# KD_Board.net
KiCad netlist of a schematic drawn in EAGLE
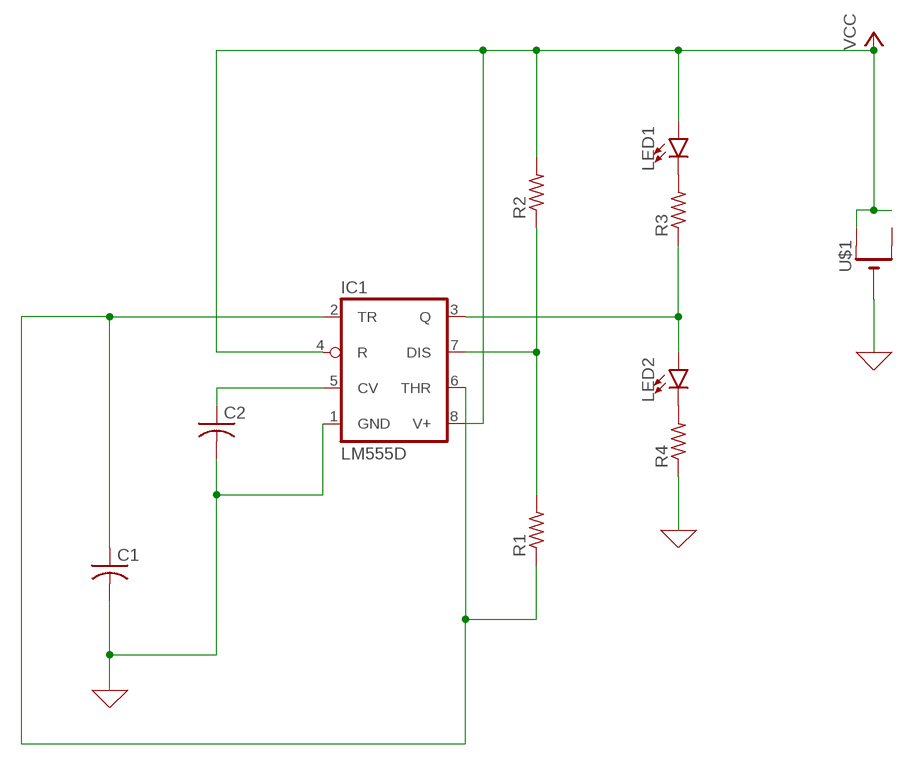
[diagram p0: schematic, sheet 1]

(export (version "E")
  (design (tool "Eeschema 10.0.6"))
  (components
    (comp (ref "C1")
      (value "C-USC0805K")
      (footprint "eagle-import:C0805K")
      (libsource (lib "eagle-import") (part "C-USC0805K"))
    )
    (comp (ref "C2")
      (value "C-USC0805K")
      (footprint "eagle-import:C0805K")
      (libsource (lib "eagle-import") (part "C-USC0805K"))
    )
    (comp (ref "IC1")
      (value "LM555D")
      (footprint "eagle-import:SO08")
      (libsource (lib "eagle-import") (part "555DLM"))
    )
    (comp (ref "LED1")
      (value "LED")
      (footprint "eagle-import:LED_5MM")
      (libsource (lib "eagle-import") (part "LED"))
    )
    (comp (ref "LED2")
      (value "LED")
      (footprint "eagle-import:LED_5MM")
      (libsource (lib "eagle-import") (part "LED"))
    )
    (comp (ref "R1")
      (value "R-US_M0805")
      (footprint "eagle-import:M0805")
      (libsource (lib "eagle-import") (part "R-US_M0805"))
    )
    (comp (ref "R2")
      (value "R-US_M0805")
      (footprint "eagle-import:M0805")
      (libsource (lib "eagle-import") (part "R-US_M0805"))
    )
    (comp (ref "R3")
      (value "R-US_M0805")
      (footprint "eagle-import:M0805")
      (libsource (lib "eagle-import") (part "R-US_M0805"))
    )
    (comp (ref "R4")
      (value "R-US_M0805")
      (footprint "eagle-import:M0805")
      (libsource (lib "eagle-import") (part "R-US_M0805"))
    )
    (comp (ref "U$1")
      (value "CR1220THM")
      (footprint "eagle-import:CR1220-THM")
      (libsource (lib "eagle-import") (part "CR1220THM"))
    )
  )
  (nets
    (net (code "1") (name "GND") (class "Default")
      (node (ref "C1") (pin "2") (pinfunction "2_2") (pintype "passive"))
      (node (ref "C2") (pin "2") (pinfunction "2_2") (pintype "passive"))
      (node (ref "IC1") (pin "1") (pinfunction "GND_1") (pintype "power_in"))
      (node (ref "R4") (pin "1") (pinfunction "1_1") (pintype "passive"))
      (node (ref "U$1") (pin "-") (pinfunction "-_-") (pintype "passive"))
    )
    (net (code "2") (name "Net-(IC1-CV)") (class "Default")
      (node (ref "C2") (pin "1") (pinfunction "1_1") (pintype "passive"))
      (node (ref "IC1") (pin "5") (pinfunction "CV_5") (pintype "input"))
    )
    (net (code "3") (name "Net-(IC1-DIS)") (class "Default")
      (node (ref "IC1") (pin "7") (pinfunction "DIS_7") (pintype "input"))
      (node (ref "R1") (pin "2") (pinfunction "2_2") (pintype "passive"))
      (node (ref "R2") (pin "1") (pinfunction "1_1") (pintype "passive"))
    )
    (net (code "4") (name "Net-(IC1-Q)") (class "Default")
      (node (ref "IC1") (pin "3") (pinfunction "Q_3") (pintype "output"))
      (node (ref "LED2") (pin "A") (pinfunction "A_A") (pintype "passive"))
      (node (ref "R3") (pin "1") (pinfunction "1_1") (pintype "passive"))
    )
    (net (code "5") (name "Net-(IC1-THR)") (class "Default")
      (node (ref "C1") (pin "1") (pinfunction "1_1") (pintype "passive"))
      (node (ref "IC1") (pin "2") (pinfunction "TR_2") (pintype "input"))
      (node (ref "IC1") (pin "6") (pinfunction "THR_6") (pintype "input"))
      (node (ref "R1") (pin "1") (pinfunction "1_1") (pintype "passive"))
    )
    (net (code "6") (name "Net-(LED1-C)") (class "Default")
      (node (ref "LED1") (pin "K") (pinfunction "C_K") (pintype "passive"))
      (node (ref "R3") (pin "2") (pinfunction "2_2") (pintype "passive"))
    )
    (net (code "7") (name "Net-(LED2-C)") (class "Default")
      (node (ref "LED2") (pin "K") (pinfunction "C_K") (pintype "passive"))
      (node (ref "R4") (pin "2") (pinfunction "2_2") (pintype "passive"))
    )
    (net (code "8") (name "VCC") (class "Default")
      (node (ref "IC1") (pin "4") (pinfunction "R_4") (pintype "input"))
      (node (ref "IC1") (pin "8") (pinfunction "V+_8") (pintype "power_in"))
      (node (ref "LED1") (pin "A") (pinfunction "A_A") (pintype "passive"))
      (node (ref "R2") (pin "2") (pinfunction "2_2") (pintype "passive"))
      (node (ref "U$1") (pin "+1") (pinfunction "+_+1") (pintype "passive"))
    )
    (net (code "9") (name "unconnected-(U$1-+1-Pad+2)") (class "Default")
      (node (ref "U$1") (pin "+2") (pinfunction "+1_+2") (pintype "passive"))
    )
  )
)
